# low-pass-filter.net
KiCad netlist of a schematic drawn in Altium Designer
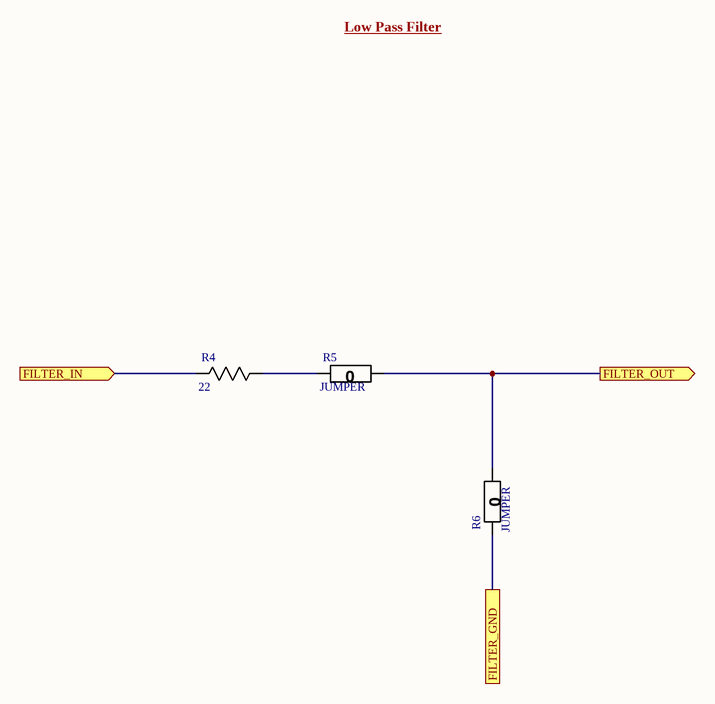
[diagram p0: low-pass-filter.SchDoc]

(export (version "E")
  (design (tool "Eeschema 10.0.6"))
  (components
    (comp (ref "R4")
      (value "22")
      (footprint "0805")
      (description "RES SMD 22 OHM 5% 1/8W 0805")
      (fields (field (name "TOLERANCE") "5%"))
      (libsource (lib "AltiumLibraries") (part "RES 22.0 1/8W"))
    )
    (comp (ref "R5")
      (value "JUMPER")
      (footprint "0805")
      (description "RES SMD 0 OHM JUMPER GENERIC 0805")
      (libsource (lib "AltiumLibraries") (part "RES 0 JUMPER"))
    )
    (comp (ref "R6")
      (value "JUMPER")
      (footprint "0805")
      (description "RES SMD 0 OHM JUMPER GENERIC 0805")
      (libsource (lib "AltiumLibraries") (part "RES 0 JUMPER"))
    )
  )
  (nets
    (net (code "1") (name "/FILTER_GND") (class "Default")
      (node (ref "R6") (pin "2") (pinfunction "R2_2") (pintype "passive"))
    )
    (net (code "2") (name "/FILTER_IN") (class "Default")
      (node (ref "R4") (pin "2") (pinfunction "R2_2") (pintype "passive"))
    )
    (net (code "3") (name "/FILTER_OUT") (class "Default")
      (node (ref "R5") (pin "1") (pinfunction "R1_1") (pintype "passive"))
      (node (ref "R6") (pin "1") (pinfunction "R1_1") (pintype "passive"))
    )
    (net (code "4") (name "Net-(R4-R1)") (class "Default")
      (node (ref "R4") (pin "1") (pinfunction "R1_1") (pintype "passive"))
      (node (ref "R5") (pin "2") (pinfunction "R2_2") (pintype "passive"))
    )
  )
)
